# 505147_2_1.net
KiCad netlist of a schematic drawn in Altium Designer
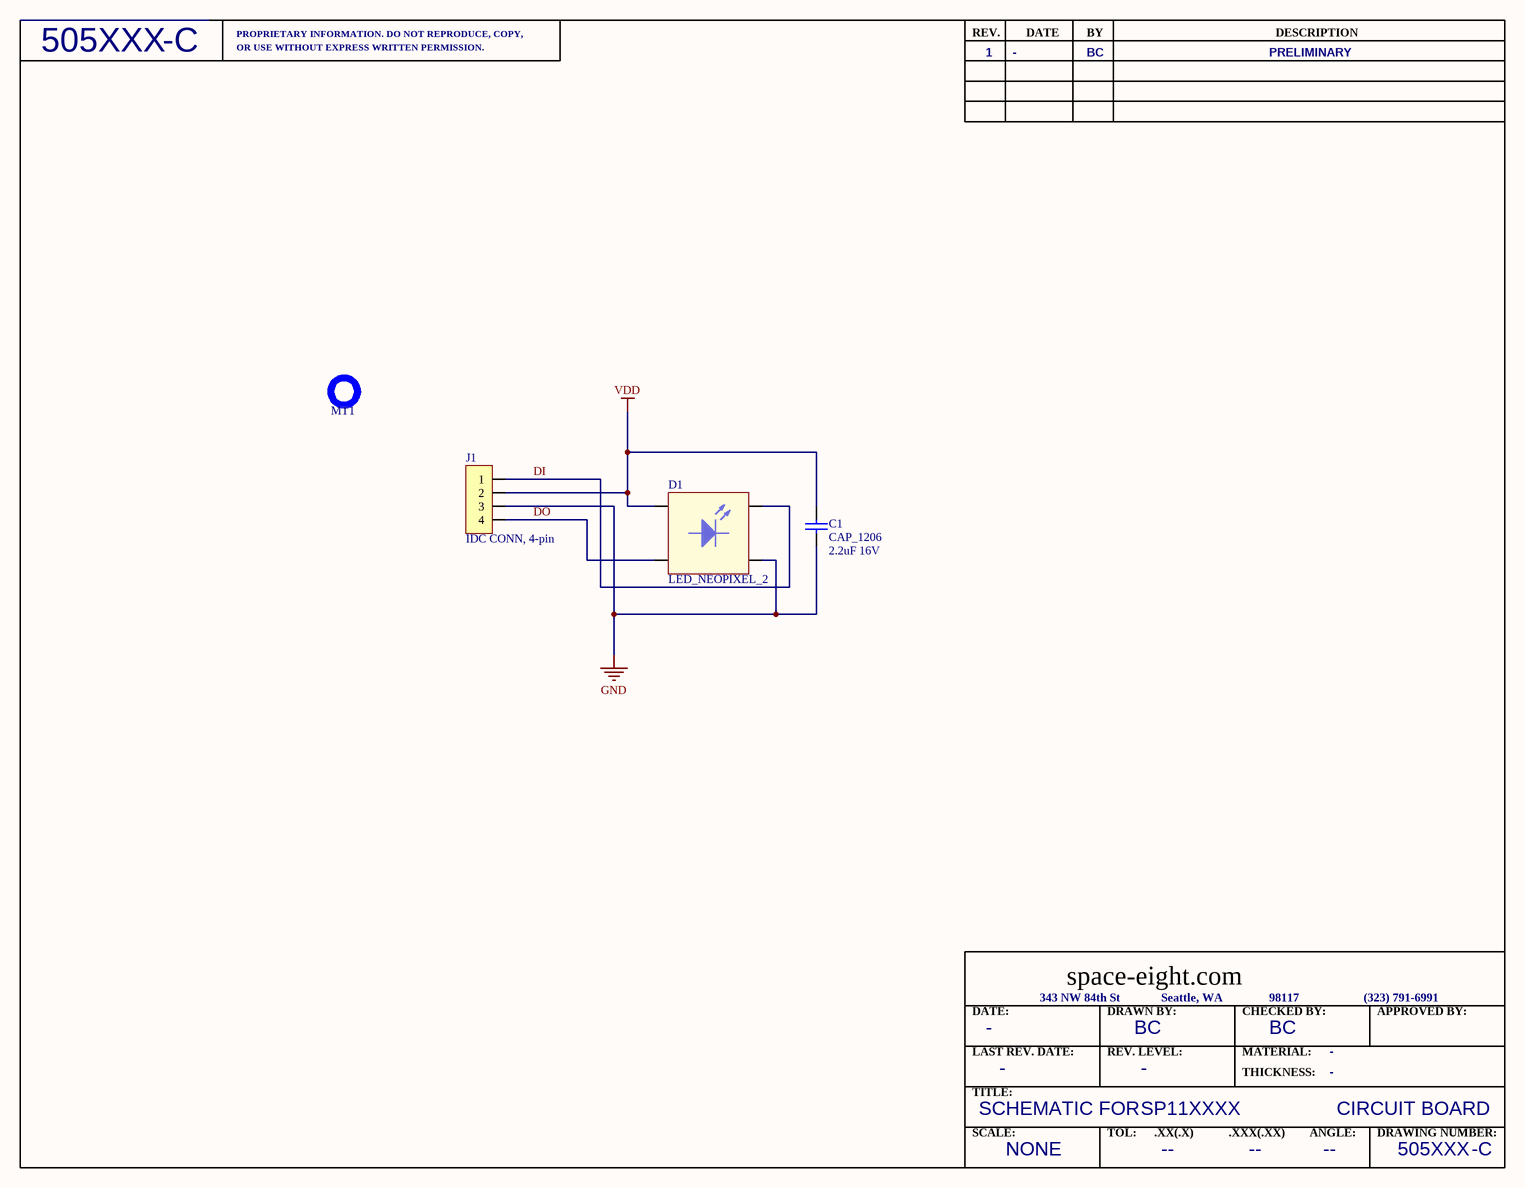
[diagram p0: 505147_2_1.SchDoc]

(export (version "E")
  (design (tool "Eeschema 10.0.6"))
  (components
    (comp (ref "C1")
      (value "CAP_1206")
      (footprint "SMT_1206_MOD")
      (description "CAP")
      (fields
        (field (name "MANUFACTURER") "Generic Components")
        (field (name "ALTIUM_VALUE") "2.2uF 16V")
        (field (name "PUBLISHER") "Altium Limited")
      )
      (libsource (lib "Custom_Lib_2") (part "CAP_1206"))
    )
    (comp (ref "D1")
      (value "LED_NEOPIXEL_2")
      (footprint "NEOPIXEL_2")
      (description "RGB NEOPIXEL")
      (fields (field (name "MANUFACTURER") "Generic Components") (field (name "PUBLISHER") "Altium Limited"))
      (libsource (lib "Custom_Lib_2") (part "LED_NEOPIXEL_2"))
    )
    (comp (ref "J1")
      (value "IDC CONN, 4-pin")
      (footprint "IDC_CONN_SMT_4-PIN")
      (description "ICD Connector, 4-Pin")
      (fields (field (name "PUBLISHER") "Altium Limited"))
      (libsource (lib "Custom_Lib_2") (part "IDC CONN, 4-pin"))
    )
    (comp (ref "MT1")
      (value "MOUNTING HOLE")
      (footprint "MOUNTING HOLE")
      (libsource (lib "Custom_Lib_2") (part "MOUNTING HOLE"))
    )
  )
  (nets
    (net (code "1") (name "/DI") (class "Default")
      (node (ref "D1") (pin "2") (pinfunction "DI_2") (pintype "passive"))
      (node (ref "J1") (pin "1") (pinfunction "1_1") (pintype "passive"))
    )
    (net (code "2") (name "/DO") (class "Default")
      (node (ref "D1") (pin "4") (pinfunction "DO_4") (pintype "passive"))
      (node (ref "J1") (pin "4") (pinfunction "4_4") (pintype "passive"))
    )
    (net (code "3") (name "GND") (class "Default")
      (node (ref "C1") (pin "1") (pinfunction "1_1") (pintype "passive"))
      (node (ref "D1") (pin "1") (pinfunction "GND_1") (pintype "passive"))
      (node (ref "J1") (pin "3") (pinfunction "3_3") (pintype "passive"))
    )
    (net (code "4") (name "VDD") (class "Default")
      (node (ref "C1") (pin "2") (pinfunction "2_2") (pintype "passive"))
      (node (ref "D1") (pin "3") (pinfunction "VDD_3") (pintype "passive"))
      (node (ref "J1") (pin "2") (pinfunction "2_2") (pintype "passive"))
    )
  )
)
